# NodoWifi_CPU0.net
KiCad netlist of a schematic drawn in Altium Designer
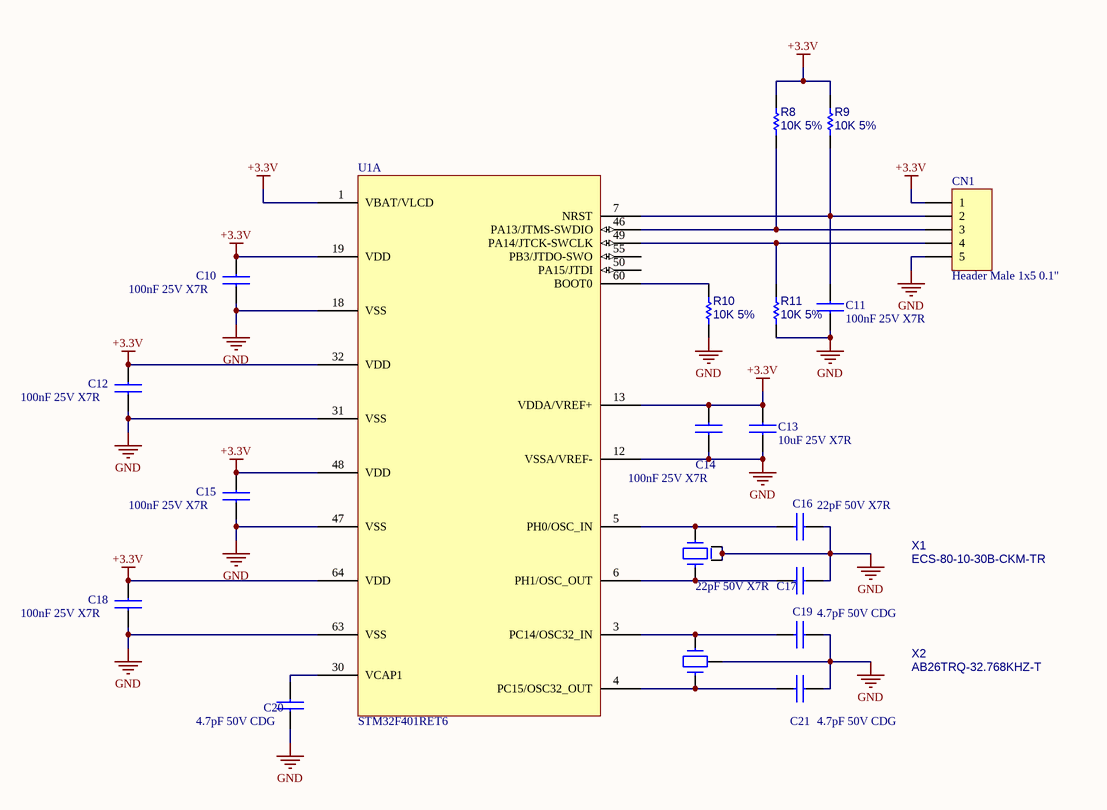
[diagram p0: NodoWifi_CPU0.SchDoc]

(export (version "E")
  (design (tool "Eeschema 10.0.6"))
  (components
    (comp (ref "C10")
      (value "100nF 25V X7R")
      (footprint "C_0805")
      (description "Ceramic Capacitor")
      (libsource (lib "NodoWifi_R00") (part "Ceramic Capacitor"))
    )
    (comp (ref "C11")
      (value "100nF 25V X7R")
      (footprint "C_0805")
      (description "Ceramic Capacitor")
      (libsource (lib "NodoWifi_R00") (part "Ceramic Capacitor"))
    )
    (comp (ref "C12")
      (value "100nF 25V X7R")
      (footprint "C_0805")
      (description "Ceramic Capacitor")
      (libsource (lib "NodoWifi_R00") (part "Ceramic Capacitor"))
    )
    (comp (ref "C13")
      (value "10uF 25V X7R")
      (footprint "C_0805")
      (description "Ceramic Capacitor")
      (libsource (lib "NodoWifi_R00") (part "Ceramic Capacitor"))
    )
    (comp (ref "C14")
      (value "100nF 25V X7R")
      (footprint "C_0805")
      (description "Ceramic Capacitor")
      (libsource (lib "NodoWifi_R00") (part "Ceramic Capacitor"))
    )
    (comp (ref "C15")
      (value "100nF 25V X7R")
      (footprint "C_0805")
      (description "Ceramic Capacitor")
      (libsource (lib "NodoWifi_R00") (part "Ceramic Capacitor"))
    )
    (comp (ref "C16")
      (value "22pF 50V X7R")
      (footprint "C_0805")
      (description "Ceramic Capacitor")
      (libsource (lib "NodoWifi_R00") (part "Ceramic Capacitor"))
    )
    (comp (ref "C17")
      (value "22pF 50V X7R")
      (footprint "C_0805")
      (description "Ceramic Capacitor")
      (libsource (lib "NodoWifi_R00") (part "Ceramic Capacitor"))
    )
    (comp (ref "C18")
      (value "100nF 25V X7R")
      (footprint "C_0805")
      (description "Ceramic Capacitor")
      (libsource (lib "NodoWifi_R00") (part "Ceramic Capacitor"))
    )
    (comp (ref "C19")
      (value "4.7pF 50V CDG")
      (footprint "C_0805")
      (description "Ceramic Capacitor")
      (libsource (lib "NodoWifi_R00") (part "Ceramic Capacitor"))
    )
    (comp (ref "C20")
      (value "4.7pF 50V CDG")
      (footprint "C_0805")
      (description "Ceramic Capacitor")
      (libsource (lib "NodoWifi_R00") (part "Ceramic Capacitor"))
    )
    (comp (ref "C21")
      (value "4.7pF 50V CDG")
      (footprint "C_0805")
      (description "Ceramic Capacitor")
      (libsource (lib "NodoWifi_R00") (part "Ceramic Capacitor"))
    )
    (comp (ref "CN1")
      (value "Header Male 1x5 0.1\"")
      (footprint "Header_M_1x5_0.1\"")
      (description "Connector Generic 5 Vias")
      (libsource (lib "NodoWifi_R00") (part "CONN_05P"))
    )
    (comp (ref "R8")
      (value "10K 5%")
      (footprint "R_0805")
      (description "Resistor")
      (libsource (lib "NodoWifi_R00") (part "Res1"))
    )
    (comp (ref "R9")
      (value "10K 5%")
      (footprint "R_0805")
      (description "Resistor")
      (libsource (lib "NodoWifi_R00") (part "Res1"))
    )
    (comp (ref "R10")
      (value "10K 5%")
      (footprint "R_0805")
      (description "Resistor")
      (libsource (lib "NodoWifi_R00") (part "Res1"))
    )
    (comp (ref "R11")
      (value "10K 5%")
      (footprint "R_0805")
      (description "Resistor")
      (libsource (lib "NodoWifi_R00") (part "Res1"))
    )
    (comp (ref "U1")
      (value "STM32F401RET6")
      (footprint "LQFP_64")
      (libsource (lib "NodoWifi_R00") (part "STM32F401RE"))
    )
    (comp (ref "X1")
      (value "ECS-80-10-30B-CKM-TR")
      (footprint "ABM3C")
      (description "Crystal 4 Vias + GND")
      (libsource (lib "NodoWifi_R00") (part "CRYSTAL_4P"))
    )
    (comp (ref "X2")
      (value "AB26TRQ-32.768KHZ-T")
      (footprint "AB26TQF")
      (description "Crystal 2 Vias + GND")
      (libsource (lib "NodoWifi_R00") (part "CRYSTAL 3P"))
    )
  )
  (nets
    (net (code "1") (name "+3.3V") (class "Default")
      (node (ref "C10") (pin "1") (pinfunction "1_1") (pintype "passive"))
      (node (ref "C12") (pin "1") (pinfunction "1_1") (pintype "passive"))
      (node (ref "C13") (pin "1") (pinfunction "1_1") (pintype "passive"))
      (node (ref "C14") (pin "1") (pinfunction "1_1") (pintype "passive"))
      (node (ref "C15") (pin "1") (pinfunction "1_1") (pintype "passive"))
      (node (ref "C18") (pin "1") (pinfunction "1_1") (pintype "passive"))
      (node (ref "CN1") (pin "1") (pinfunction "1_1") (pintype "passive"))
      (node (ref "R8") (pin "2") (pinfunction "2_2") (pintype "passive"))
      (node (ref "R9") (pin "2") (pinfunction "2_2") (pintype "passive"))
      (node (ref "U1") (pin "1") (pinfunction "VBAT/VLCD_1") (pintype "passive"))
      (node (ref "U1") (pin "13") (pinfunction "VDDA/VREF+_13") (pintype "passive"))
      (node (ref "U1") (pin "19") (pinfunction "VDD_19") (pintype "passive"))
      (node (ref "U1") (pin "32") (pinfunction "VDD_32") (pintype "passive"))
      (node (ref "U1") (pin "48") (pinfunction "VDD_48") (pintype "passive"))
      (node (ref "U1") (pin "64") (pinfunction "VDD_64") (pintype "passive"))
    )
    (net (code "2") (name "GND") (class "Default")
      (node (ref "C10") (pin "2") (pinfunction "2_2") (pintype "passive"))
      (node (ref "C11") (pin "2") (pinfunction "2_2") (pintype "passive"))
      (node (ref "C12") (pin "2") (pinfunction "2_2") (pintype "passive"))
      (node (ref "C13") (pin "2") (pinfunction "2_2") (pintype "passive"))
      (node (ref "C14") (pin "2") (pinfunction "2_2") (pintype "passive"))
      (node (ref "C15") (pin "2") (pinfunction "2_2") (pintype "passive"))
      (node (ref "C16") (pin "2") (pinfunction "2_2") (pintype "passive"))
      (node (ref "C17") (pin "2") (pinfunction "2_2") (pintype "passive"))
      (node (ref "C18") (pin "2") (pinfunction "2_2") (pintype "passive"))
      (node (ref "C19") (pin "2") (pinfunction "2_2") (pintype "passive"))
      (node (ref "C20") (pin "1") (pinfunction "1_1") (pintype "passive"))
      (node (ref "C21") (pin "2") (pinfunction "2_2") (pintype "passive"))
      (node (ref "CN1") (pin "5") (pinfunction "5_5") (pintype "passive"))
      (node (ref "R10") (pin "1") (pinfunction "1_1") (pintype "passive"))
      (node (ref "R11") (pin "1") (pinfunction "1_1") (pintype "passive"))
      (node (ref "U1") (pin "12") (pinfunction "VSSA/VREF-_12") (pintype "passive"))
      (node (ref "U1") (pin "18") (pinfunction "VSS_18") (pintype "passive"))
      (node (ref "U1") (pin "31") (pinfunction "VSS_31") (pintype "passive"))
      (node (ref "U1") (pin "47") (pinfunction "VSS_47") (pintype "passive"))
      (node (ref "U1") (pin "63") (pinfunction "VSS_63") (pintype "passive"))
      (node (ref "X1") (pin "2") (pinfunction "2_2") (pintype "passive"))
      (node (ref "X1") (pin "4") (pinfunction "4_4") (pintype "passive"))
      (node (ref "X2") (pin "3") (pinfunction "3_3") (pintype "passive"))
    )
    (net (code "3") (name "Net-(U1A-BOOT0)") (class "Default")
      (node (ref "R10") (pin "2") (pinfunction "2_2") (pintype "passive"))
      (node (ref "U1") (pin "60") (pinfunction "BOOT0_60") (pintype "passive"))
    )
    (net (code "4") (name "Net-(U1A-NRST)") (class "Default")
      (node (ref "C11") (pin "1") (pinfunction "1_1") (pintype "passive"))
      (node (ref "CN1") (pin "2") (pinfunction "2_2") (pintype "passive"))
      (node (ref "R9") (pin "1") (pinfunction "1_1") (pintype "passive"))
      (node (ref "U1") (pin "7") (pinfunction "NRST_7") (pintype "passive"))
    )
    (net (code "5") (name "Net-(U1A-PA13{slash}JTMS-SWDIO)") (class "Default")
      (node (ref "CN1") (pin "3") (pinfunction "3_3") (pintype "passive"))
      (node (ref "R8") (pin "1") (pinfunction "1_1") (pintype "passive"))
      (node (ref "U1") (pin "46") (pinfunction "PA13/JTMS-SWDIO_46") (pintype "bidirectional"))
    )
    (net (code "6") (name "Net-(U1A-PA14{slash}JTCK-SWCLK)") (class "Default")
      (node (ref "CN1") (pin "4") (pinfunction "4_4") (pintype "passive"))
      (node (ref "R11") (pin "2") (pinfunction "2_2") (pintype "passive"))
      (node (ref "U1") (pin "49") (pinfunction "PA14/JTCK-SWCLK_49") (pintype "bidirectional"))
    )
    (net (code "7") (name "Net-(U1A-PC14{slash}OSC32_IN)") (class "Default")
      (node (ref "C19") (pin "1") (pinfunction "1_1") (pintype "passive"))
      (node (ref "U1") (pin "3") (pinfunction "PC14/OSC32_IN_3") (pintype "passive"))
      (node (ref "X2") (pin "2") (pinfunction "2_2") (pintype "passive"))
    )
    (net (code "8") (name "Net-(U1A-PC15{slash}OSC32_OUT)") (class "Default")
      (node (ref "C21") (pin "1") (pinfunction "1_1") (pintype "passive"))
      (node (ref "U1") (pin "4") (pinfunction "PC15/OSC32_OUT_4") (pintype "passive"))
      (node (ref "X2") (pin "1") (pinfunction "1_1") (pintype "passive"))
    )
    (net (code "9") (name "Net-(U1A-PH0{slash}OSC_IN)") (class "Default")
      (node (ref "C16") (pin "1") (pinfunction "1_1") (pintype "passive"))
      (node (ref "U1") (pin "5") (pinfunction "PH0/OSC_IN_5") (pintype "passive"))
      (node (ref "X1") (pin "1") (pinfunction "1_1") (pintype "passive"))
    )
    (net (code "10") (name "Net-(U1A-PH1{slash}OSC_OUT)") (class "Default")
      (node (ref "C17") (pin "1") (pinfunction "1_1") (pintype "passive"))
      (node (ref "U1") (pin "6") (pinfunction "PH1/OSC_OUT_6") (pintype "passive"))
      (node (ref "X1") (pin "3") (pinfunction "3_3") (pintype "passive"))
    )
    (net (code "11") (name "Net-(U1A-VCAP1)") (class "Default")
      (node (ref "C20") (pin "2") (pinfunction "2_2") (pintype "passive"))
      (node (ref "U1") (pin "30") (pinfunction "VCAP1_30") (pintype "passive"))
    )
    (net (code "12") (name "unconnected-(U1A-PA15{slash}JTDI-Pad50)") (class "Default")
      (node (ref "U1") (pin "50") (pinfunction "PA15/JTDI_50") (pintype "bidirectional"))
    )
    (net (code "13") (name "unconnected-(U1A-PB3{slash}JTDO-SWO-Pad55)") (class "Default")
      (node (ref "U1") (pin "55") (pinfunction "PB3/JTDO-SWO_55") (pintype "bidirectional"))
    )
  )
)
